# sch2.net
KiCad netlist of a schematic drawn in EAGLE
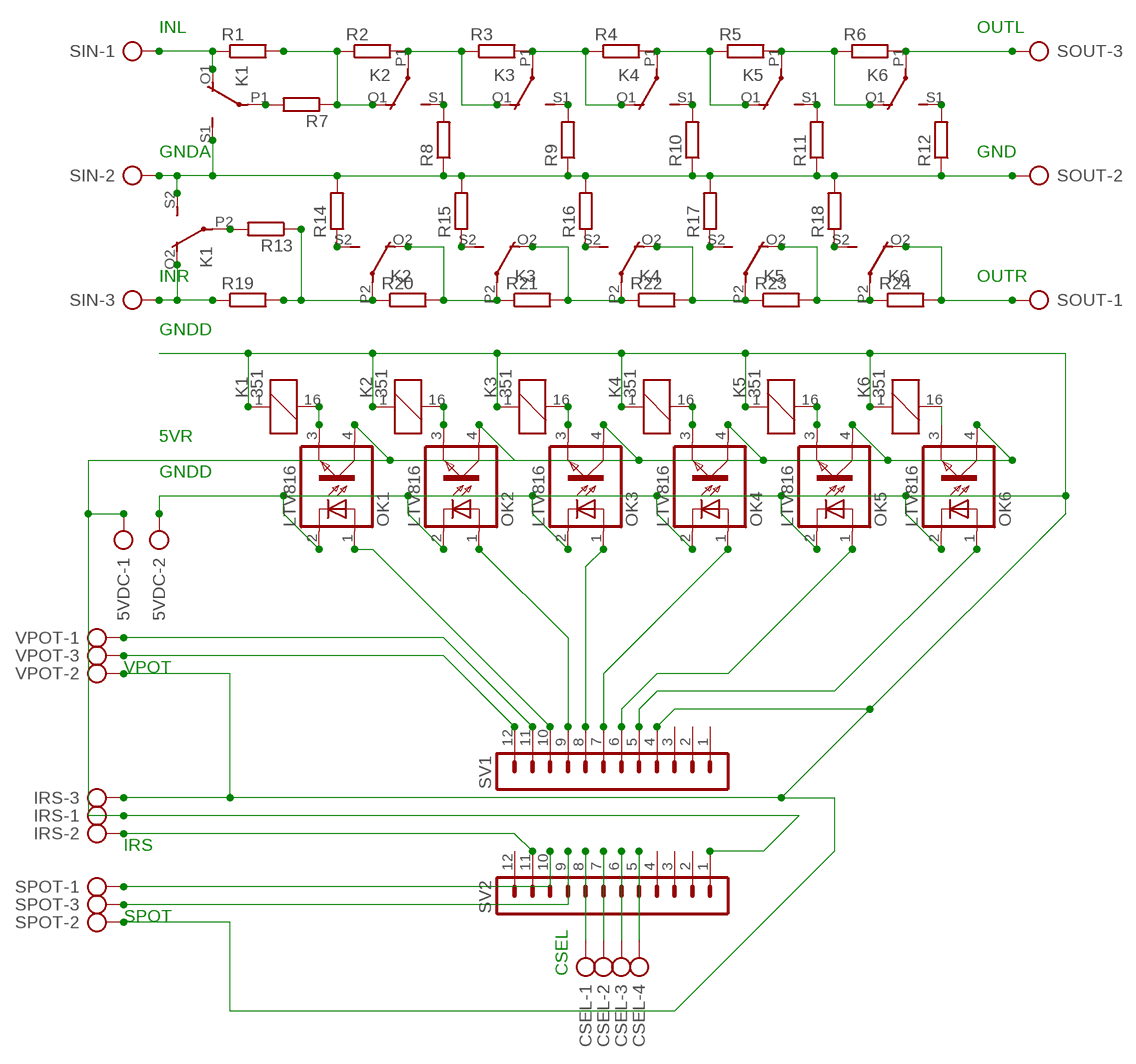
[diagram p0: schematic, sheet 1]

(export (version "E")
  (design (tool "Eeschema 10.0.6"))
  (components
    (comp (ref "5VDC")
      (value "AK500/2")
      (footprint "eagle-import:AK500_2")
      (libsource (lib "eagle-import") (part "AK500/2"))
    )
    (comp (ref "CSEL")
      (value "AK500/4")
      (footprint "eagle-import:AK500_4")
      (libsource (lib "eagle-import") (part "AK500/4"))
    )
    (comp (ref "IRS")
      (value "AK500/3")
      (footprint "eagle-import:AK500_3")
      (libsource (lib "eagle-import") (part "AK500/3"))
    )
    (comp (ref "K1")
      (value "351")
      (footprint "eagle-import:351")
      (libsource (lib "eagle-import") (part "351"))
    )
    (comp (ref "K2")
      (value "351")
      (footprint "eagle-import:351")
      (libsource (lib "eagle-import") (part "351"))
    )
    (comp (ref "K3")
      (value "351")
      (footprint "eagle-import:351")
      (libsource (lib "eagle-import") (part "351"))
    )
    (comp (ref "K4")
      (value "351")
      (footprint "eagle-import:351")
      (libsource (lib "eagle-import") (part "351"))
    )
    (comp (ref "K5")
      (value "351")
      (footprint "eagle-import:351")
      (libsource (lib "eagle-import") (part "351"))
    )
    (comp (ref "K6")
      (value "351")
      (footprint "eagle-import:351")
      (libsource (lib "eagle-import") (part "351"))
    )
    (comp (ref "OK1")
      (value "LTV816")
      (footprint "eagle-import:DIL04")
      (libsource (lib "eagle-import") (part "LTV816"))
    )
    (comp (ref "OK2")
      (value "LTV816")
      (footprint "eagle-import:DIL04")
      (libsource (lib "eagle-import") (part "LTV816"))
    )
    (comp (ref "OK3")
      (value "LTV816")
      (footprint "eagle-import:DIL04")
      (libsource (lib "eagle-import") (part "LTV816"))
    )
    (comp (ref "OK4")
      (value "LTV816")
      (footprint "eagle-import:DIL04")
      (libsource (lib "eagle-import") (part "LTV816"))
    )
    (comp (ref "OK5")
      (value "LTV816")
      (footprint "eagle-import:DIL04")
      (libsource (lib "eagle-import") (part "LTV816"))
    )
    (comp (ref "OK6")
      (value "LTV816")
      (footprint "eagle-import:DIL04")
      (libsource (lib "eagle-import") (part "LTV816"))
    )
    (comp (ref "R1")
      (value "R-EU_0204/7")
      (footprint "eagle-import:0204_7")
      (libsource (lib "eagle-import") (part "R-EU_0204/7"))
    )
    (comp (ref "R2")
      (value "R-EU_0204/7")
      (footprint "eagle-import:0204_7")
      (libsource (lib "eagle-import") (part "R-EU_0204/7"))
    )
    (comp (ref "R3")
      (value "R-EU_0204/7")
      (footprint "eagle-import:0204_7")
      (libsource (lib "eagle-import") (part "R-EU_0204/7"))
    )
    (comp (ref "R4")
      (value "R-EU_0204/7")
      (footprint "eagle-import:0204_7")
      (libsource (lib "eagle-import") (part "R-EU_0204/7"))
    )
    (comp (ref "R5")
      (value "R-EU_0204/7")
      (footprint "eagle-import:0204_7")
      (libsource (lib "eagle-import") (part "R-EU_0204/7"))
    )
    (comp (ref "R6")
      (value "R-EU_0204/7")
      (footprint "eagle-import:0204_7")
      (libsource (lib "eagle-import") (part "R-EU_0204/7"))
    )
    (comp (ref "R7")
      (value "R-EU_0204/7")
      (footprint "eagle-import:0204_7")
      (libsource (lib "eagle-import") (part "R-EU_0204/7"))
    )
    (comp (ref "R8")
      (value "R-EU_0204/7")
      (footprint "eagle-import:0204_7")
      (libsource (lib "eagle-import") (part "R-EU_0204/7"))
    )
    (comp (ref "R9")
      (value "R-EU_0204/7")
      (footprint "eagle-import:0204_7")
      (libsource (lib "eagle-import") (part "R-EU_0204/7"))
    )
    (comp (ref "R10")
      (value "R-EU_0204/7")
      (footprint "eagle-import:0204_7")
      (libsource (lib "eagle-import") (part "R-EU_0204/7"))
    )
    (comp (ref "R11")
      (value "R-EU_0204/7")
      (footprint "eagle-import:0204_7")
      (libsource (lib "eagle-import") (part "R-EU_0204/7"))
    )
    (comp (ref "R12")
      (value "R-EU_0204/7")
      (footprint "eagle-import:0204_7")
      (libsource (lib "eagle-import") (part "R-EU_0204/7"))
    )
    (comp (ref "R13")
      (value "R-EU_0204/7")
      (footprint "eagle-import:0204_7")
      (libsource (lib "eagle-import") (part "R-EU_0204/7"))
    )
    (comp (ref "R14")
      (value "R-EU_0204/7")
      (footprint "eagle-import:0204_7")
      (libsource (lib "eagle-import") (part "R-EU_0204/7"))
    )
    (comp (ref "R15")
      (value "R-EU_0204/7")
      (footprint "eagle-import:0204_7")
      (libsource (lib "eagle-import") (part "R-EU_0204/7"))
    )
    (comp (ref "R16")
      (value "R-EU_0204/7")
      (footprint "eagle-import:0204_7")
      (libsource (lib "eagle-import") (part "R-EU_0204/7"))
    )
    (comp (ref "R17")
      (value "R-EU_0204/7")
      (footprint "eagle-import:0204_7")
      (libsource (lib "eagle-import") (part "R-EU_0204/7"))
    )
    (comp (ref "R18")
      (value "R-EU_0204/7")
      (footprint "eagle-import:0204_7")
      (libsource (lib "eagle-import") (part "R-EU_0204/7"))
    )
    (comp (ref "R19")
      (value "R-EU_0204/7")
      (footprint "eagle-import:0204_7")
      (libsource (lib "eagle-import") (part "R-EU_0204/7"))
    )
    (comp (ref "R20")
      (value "R-EU_0204/7")
      (footprint "eagle-import:0204_7")
      (libsource (lib "eagle-import") (part "R-EU_0204/7"))
    )
    (comp (ref "R21")
      (value "R-EU_0204/7")
      (footprint "eagle-import:0204_7")
      (libsource (lib "eagle-import") (part "R-EU_0204/7"))
    )
    (comp (ref "R22")
      (value "R-EU_0204/7")
      (footprint "eagle-import:0204_7")
      (libsource (lib "eagle-import") (part "R-EU_0204/7"))
    )
    (comp (ref "R23")
      (value "R-EU_0204/7")
      (footprint "eagle-import:0204_7")
      (libsource (lib "eagle-import") (part "R-EU_0204/7"))
    )
    (comp (ref "R24")
      (value "R-EU_0204/7")
      (footprint "eagle-import:0204_7")
      (libsource (lib "eagle-import") (part "R-EU_0204/7"))
    )
    (comp (ref "SIN")
      (value "AK500/3")
      (footprint "eagle-import:AK500_3")
      (libsource (lib "eagle-import") (part "AK500/3"))
    )
    (comp (ref "SOUT")
      (value "AK500/3")
      (footprint "eagle-import:AK500_3")
      (libsource (lib "eagle-import") (part "AK500/3"))
    )
    (comp (ref "SPOT")
      (value "AK500/3")
      (footprint "eagle-import:AK500_3")
      (libsource (lib "eagle-import") (part "AK500/3"))
    )
    (comp (ref "SV1")
      (value "MA12-1")
      (footprint "eagle-import:MA12-1")
      (libsource (lib "eagle-import") (part "MA12-1"))
    )
    (comp (ref "SV2")
      (value "MA12-1")
      (footprint "eagle-import:MA12-1")
      (libsource (lib "eagle-import") (part "MA12-1"))
    )
    (comp (ref "VPOT")
      (value "AK500/3")
      (footprint "eagle-import:AK500_3")
      (libsource (lib "eagle-import") (part "AK500/3"))
    )
  )
  (nets
    (net (code "1") (name "Net-(5VDCA-KL)") (class "Default")
      (node (ref "5VDC") (pin "1") (pinfunction "KL_1") (pintype "passive"))
      (node (ref "IRS") (pin "1") (pinfunction "KL_1") (pintype "passive"))
      (node (ref "OK1") (pin "4") (pinfunction "COL_4") (pintype "passive"))
      (node (ref "OK2") (pin "4") (pinfunction "COL_4") (pintype "passive"))
      (node (ref "OK3") (pin "4") (pinfunction "COL_4") (pintype "passive"))
      (node (ref "OK4") (pin "4") (pinfunction "COL_4") (pintype "passive"))
      (node (ref "OK5") (pin "4") (pinfunction "COL_4") (pintype "passive"))
      (node (ref "OK6") (pin "4") (pinfunction "COL_4") (pintype "passive"))
      (node (ref "SV2") (pin "1") (pinfunction "1_1") (pintype "passive"))
    )
    (net (code "2") (name "Net-(5VDCB-KL)") (class "Default")
      (node (ref "5VDC") (pin "2") (pinfunction "KL_2") (pintype "passive"))
      (node (ref "IRS") (pin "3") (pinfunction "KL_3") (pintype "passive"))
      (node (ref "K1") (pin "1") (pinfunction "1_1") (pintype "passive"))
      (node (ref "K2") (pin "1") (pinfunction "1_1") (pintype "passive"))
      (node (ref "K3") (pin "1") (pinfunction "1_1") (pintype "passive"))
      (node (ref "K4") (pin "1") (pinfunction "1_1") (pintype "passive"))
      (node (ref "K5") (pin "1") (pinfunction "1_1") (pintype "passive"))
      (node (ref "K6") (pin "1") (pinfunction "1_1") (pintype "passive"))
      (node (ref "OK1") (pin "2") (pinfunction "C_2") (pintype "passive"))
      (node (ref "OK2") (pin "2") (pinfunction "C_2") (pintype "passive"))
      (node (ref "OK3") (pin "2") (pinfunction "C_2") (pintype "passive"))
      (node (ref "OK4") (pin "2") (pinfunction "C_2") (pintype "passive"))
      (node (ref "OK5") (pin "2") (pinfunction "C_2") (pintype "passive"))
      (node (ref "OK6") (pin "2") (pinfunction "C_2") (pintype "passive"))
      (node (ref "SPOT") (pin "2") (pinfunction "KL_2") (pintype "passive"))
      (node (ref "SV1") (pin "4") (pinfunction "4_4") (pintype "passive"))
      (node (ref "VPOT") (pin "2") (pinfunction "KL_2") (pintype "passive"))
    )
    (net (code "3") (name "Net-(CSELA-KL)") (class "Default")
      (node (ref "CSEL") (pin "1") (pinfunction "KL_1") (pintype "passive"))
      (node (ref "SV2") (pin "8") (pinfunction "8_8") (pintype "passive"))
    )
    (net (code "4") (name "Net-(CSELB-KL)") (class "Default")
      (node (ref "CSEL") (pin "2") (pinfunction "KL_2") (pintype "passive"))
      (node (ref "SV2") (pin "7") (pinfunction "7_7") (pintype "passive"))
    )
    (net (code "5") (name "Net-(CSELC-KL)") (class "Default")
      (node (ref "CSEL") (pin "3") (pinfunction "KL_3") (pintype "passive"))
      (node (ref "SV2") (pin "6") (pinfunction "6_6") (pintype "passive"))
    )
    (net (code "6") (name "Net-(CSELD-KL)") (class "Default")
      (node (ref "CSEL") (pin "4") (pinfunction "KL_4") (pintype "passive"))
      (node (ref "SV2") (pin "5") (pinfunction "5_5") (pintype "passive"))
    )
    (net (code "7") (name "Net-(IRSB-KL)") (class "Default")
      (node (ref "IRS") (pin "2") (pinfunction "KL_2") (pintype "passive"))
      (node (ref "SV2") (pin "11") (pinfunction "11_11") (pintype "passive"))
    )
    (net (code "8") (name "Net-(K1A-2)") (class "Default")
      (node (ref "K1") (pin "16") (pinfunction "2_16") (pintype "passive"))
      (node (ref "OK1") (pin "3") (pinfunction "EMIT_3") (pintype "passive"))
    )
    (net (code "9") (name "Net-(K1B-O)") (class "Default")
      (node (ref "K1") (pin "O1") (pinfunction "O_O1") (pintype "passive"))
      (node (ref "R1") (pin "1") (pinfunction "1_1") (pintype "passive"))
      (node (ref "SIN") (pin "1") (pinfunction "KL_1") (pintype "passive"))
    )
    (net (code "10") (name "Net-(K1B-P)") (class "Default")
      (node (ref "K1") (pin "P1") (pinfunction "P_P1") (pintype "passive"))
      (node (ref "R7") (pin "2") (pinfunction "2_2") (pintype "passive"))
    )
    (net (code "11") (name "Net-(K1B-S)") (class "Default")
      (node (ref "K1") (pin "S1") (pinfunction "S_S1") (pintype "passive"))
      (node (ref "K1") (pin "S2") (pinfunction "S_S2") (pintype "passive"))
      (node (ref "R10") (pin "1") (pinfunction "1_1") (pintype "passive"))
      (node (ref "R11") (pin "1") (pinfunction "1_1") (pintype "passive"))
      (node (ref "R12") (pin "1") (pinfunction "1_1") (pintype "passive"))
      (node (ref "R14") (pin "2") (pinfunction "2_2") (pintype "passive"))
      (node (ref "R15") (pin "2") (pinfunction "2_2") (pintype "passive"))
      (node (ref "R16") (pin "2") (pinfunction "2_2") (pintype "passive"))
      (node (ref "R17") (pin "2") (pinfunction "2_2") (pintype "passive"))
      (node (ref "R18") (pin "2") (pinfunction "2_2") (pintype "passive"))
      (node (ref "R8") (pin "1") (pinfunction "1_1") (pintype "passive"))
      (node (ref "R9") (pin "1") (pinfunction "1_1") (pintype "passive"))
      (node (ref "SIN") (pin "2") (pinfunction "KL_2") (pintype "passive"))
      (node (ref "SOUT") (pin "2") (pinfunction "KL_2") (pintype "passive"))
    )
    (net (code "12") (name "Net-(K1C-O)") (class "Default")
      (node (ref "K1") (pin "O2") (pinfunction "O_O2") (pintype "passive"))
      (node (ref "R19") (pin "1") (pinfunction "1_1") (pintype "passive"))
      (node (ref "SIN") (pin "3") (pinfunction "KL_3") (pintype "passive"))
    )
    (net (code "13") (name "Net-(K1C-P)") (class "Default")
      (node (ref "K1") (pin "P2") (pinfunction "P_P2") (pintype "passive"))
      (node (ref "R13") (pin "2") (pinfunction "2_2") (pintype "passive"))
    )
    (net (code "14") (name "Net-(K2A-2)") (class "Default")
      (node (ref "K2") (pin "16") (pinfunction "2_16") (pintype "passive"))
      (node (ref "OK2") (pin "3") (pinfunction "EMIT_3") (pintype "passive"))
    )
    (net (code "15") (name "Net-(K2B-O)") (class "Default")
      (node (ref "K2") (pin "O1") (pinfunction "O_O1") (pintype "passive"))
      (node (ref "R1") (pin "2") (pinfunction "2_2") (pintype "passive"))
      (node (ref "R2") (pin "1") (pinfunction "1_1") (pintype "passive"))
      (node (ref "R7") (pin "1") (pinfunction "1_1") (pintype "passive"))
    )
    (net (code "16") (name "Net-(K2B-P)") (class "Default")
      (node (ref "K2") (pin "P1") (pinfunction "P_P1") (pintype "passive"))
      (node (ref "K3") (pin "O1") (pinfunction "O_O1") (pintype "passive"))
      (node (ref "R2") (pin "2") (pinfunction "2_2") (pintype "passive"))
      (node (ref "R3") (pin "1") (pinfunction "1_1") (pintype "passive"))
    )
    (net (code "17") (name "Net-(K2B-S)") (class "Default")
      (node (ref "K2") (pin "S1") (pinfunction "S_S1") (pintype "passive"))
      (node (ref "R8") (pin "2") (pinfunction "2_2") (pintype "passive"))
    )
    (net (code "18") (name "Net-(K2C-O)") (class "Default")
      (node (ref "K2") (pin "O2") (pinfunction "O_O2") (pintype "passive"))
      (node (ref "K3") (pin "P2") (pinfunction "P_P2") (pintype "passive"))
      (node (ref "R20") (pin "2") (pinfunction "2_2") (pintype "passive"))
      (node (ref "R21") (pin "1") (pinfunction "1_1") (pintype "passive"))
    )
    (net (code "19") (name "Net-(K2C-P)") (class "Default")
      (node (ref "K2") (pin "P2") (pinfunction "P_P2") (pintype "passive"))
      (node (ref "R13") (pin "1") (pinfunction "1_1") (pintype "passive"))
      (node (ref "R19") (pin "2") (pinfunction "2_2") (pintype "passive"))
      (node (ref "R20") (pin "1") (pinfunction "1_1") (pintype "passive"))
    )
    (net (code "20") (name "Net-(K2C-S)") (class "Default")
      (node (ref "K2") (pin "S2") (pinfunction "S_S2") (pintype "passive"))
      (node (ref "R14") (pin "1") (pinfunction "1_1") (pintype "passive"))
    )
    (net (code "21") (name "Net-(K3A-2)") (class "Default")
      (node (ref "K3") (pin "16") (pinfunction "2_16") (pintype "passive"))
      (node (ref "OK3") (pin "3") (pinfunction "EMIT_3") (pintype "passive"))
    )
    (net (code "22") (name "Net-(K3B-P)") (class "Default")
      (node (ref "K3") (pin "P1") (pinfunction "P_P1") (pintype "passive"))
      (node (ref "K4") (pin "O1") (pinfunction "O_O1") (pintype "passive"))
      (node (ref "R3") (pin "2") (pinfunction "2_2") (pintype "passive"))
      (node (ref "R4") (pin "1") (pinfunction "1_1") (pintype "passive"))
    )
    (net (code "23") (name "Net-(K3B-S)") (class "Default")
      (node (ref "K3") (pin "S1") (pinfunction "S_S1") (pintype "passive"))
      (node (ref "R9") (pin "2") (pinfunction "2_2") (pintype "passive"))
    )
    (net (code "24") (name "Net-(K3C-O)") (class "Default")
      (node (ref "K3") (pin "O2") (pinfunction "O_O2") (pintype "passive"))
      (node (ref "K4") (pin "P2") (pinfunction "P_P2") (pintype "passive"))
      (node (ref "R21") (pin "2") (pinfunction "2_2") (pintype "passive"))
      (node (ref "R22") (pin "1") (pinfunction "1_1") (pintype "passive"))
    )
    (net (code "25") (name "Net-(K3C-S)") (class "Default")
      (node (ref "K3") (pin "S2") (pinfunction "S_S2") (pintype "passive"))
      (node (ref "R15") (pin "1") (pinfunction "1_1") (pintype "passive"))
    )
    (net (code "26") (name "Net-(K4A-2)") (class "Default")
      (node (ref "K4") (pin "16") (pinfunction "2_16") (pintype "passive"))
      (node (ref "OK4") (pin "3") (pinfunction "EMIT_3") (pintype "passive"))
    )
    (net (code "27") (name "Net-(K4B-P)") (class "Default")
      (node (ref "K4") (pin "P1") (pinfunction "P_P1") (pintype "passive"))
      (node (ref "K5") (pin "O1") (pinfunction "O_O1") (pintype "passive"))
      (node (ref "R4") (pin "2") (pinfunction "2_2") (pintype "passive"))
      (node (ref "R5") (pin "1") (pinfunction "1_1") (pintype "passive"))
    )
    (net (code "28") (name "Net-(K4B-S)") (class "Default")
      (node (ref "K4") (pin "S1") (pinfunction "S_S1") (pintype "passive"))
      (node (ref "R10") (pin "2") (pinfunction "2_2") (pintype "passive"))
    )
    (net (code "29") (name "Net-(K4C-O)") (class "Default")
      (node (ref "K4") (pin "O2") (pinfunction "O_O2") (pintype "passive"))
      (node (ref "K5") (pin "P2") (pinfunction "P_P2") (pintype "passive"))
      (node (ref "R22") (pin "2") (pinfunction "2_2") (pintype "passive"))
      (node (ref "R23") (pin "1") (pinfunction "1_1") (pintype "passive"))
    )
    (net (code "30") (name "Net-(K4C-S)") (class "Default")
      (node (ref "K4") (pin "S2") (pinfunction "S_S2") (pintype "passive"))
      (node (ref "R16") (pin "1") (pinfunction "1_1") (pintype "passive"))
    )
    (net (code "31") (name "Net-(K5A-2)") (class "Default")
      (node (ref "K5") (pin "16") (pinfunction "2_16") (pintype "passive"))
      (node (ref "OK5") (pin "3") (pinfunction "EMIT_3") (pintype "passive"))
    )
    (net (code "32") (name "Net-(K5B-P)") (class "Default")
      (node (ref "K5") (pin "P1") (pinfunction "P_P1") (pintype "passive"))
      (node (ref "K6") (pin "O1") (pinfunction "O_O1") (pintype "passive"))
      (node (ref "R5") (pin "2") (pinfunction "2_2") (pintype "passive"))
      (node (ref "R6") (pin "1") (pinfunction "1_1") (pintype "passive"))
    )
    (net (code "33") (name "Net-(K5B-S)") (class "Default")
      (node (ref "K5") (pin "S1") (pinfunction "S_S1") (pintype "passive"))
      (node (ref "R11") (pin "2") (pinfunction "2_2") (pintype "passive"))
    )
    (net (code "34") (name "Net-(K5C-O)") (class "Default")
      (node (ref "K5") (pin "O2") (pinfunction "O_O2") (pintype "passive"))
      (node (ref "K6") (pin "P2") (pinfunction "P_P2") (pintype "passive"))
      (node (ref "R23") (pin "2") (pinfunction "2_2") (pintype "passive"))
      (node (ref "R24") (pin "1") (pinfunction "1_1") (pintype "passive"))
    )
    (net (code "35") (name "Net-(K5C-S)") (class "Default")
      (node (ref "K5") (pin "S2") (pinfunction "S_S2") (pintype "passive"))
      (node (ref "R17") (pin "1") (pinfunction "1_1") (pintype "passive"))
    )
    (net (code "36") (name "Net-(K6A-2)") (class "Default")
      (node (ref "K6") (pin "16") (pinfunction "2_16") (pintype "passive"))
      (node (ref "OK6") (pin "3") (pinfunction "EMIT_3") (pintype "passive"))
    )
    (net (code "37") (name "Net-(K6B-P)") (class "Default")
      (node (ref "K6") (pin "P1") (pinfunction "P_P1") (pintype "passive"))
      (node (ref "R6") (pin "2") (pinfunction "2_2") (pintype "passive"))
      (node (ref "SOUT") (pin "3") (pinfunction "KL_3") (pintype "passive"))
    )
    (net (code "38") (name "Net-(K6B-S)") (class "Default")
      (node (ref "K6") (pin "S1") (pinfunction "S_S1") (pintype "passive"))
      (node (ref "R12") (pin "2") (pinfunction "2_2") (pintype "passive"))
    )
    (net (code "39") (name "Net-(K6C-O)") (class "Default")
      (node (ref "K6") (pin "O2") (pinfunction "O_O2") (pintype "passive"))
      (node (ref "R24") (pin "2") (pinfunction "2_2") (pintype "passive"))
      (node (ref "SOUT") (pin "1") (pinfunction "KL_1") (pintype "passive"))
    )
    (net (code "40") (name "Net-(K6C-S)") (class "Default")
      (node (ref "K6") (pin "S2") (pinfunction "S_S2") (pintype "passive"))
      (node (ref "R18") (pin "1") (pinfunction "1_1") (pintype "passive"))
    )
    (net (code "41") (name "Net-(OK1-A)") (class "Default")
      (node (ref "OK1") (pin "1") (pinfunction "A_1") (pintype "passive"))
      (node (ref "SV1") (pin "10") (pinfunction "10_10") (pintype "passive"))
    )
    (net (code "42") (name "Net-(OK2-A)") (class "Default")
      (node (ref "OK2") (pin "1") (pinfunction "A_1") (pintype "passive"))
      (node (ref "SV1") (pin "9") (pinfunction "9_9") (pintype "passive"))
    )
    (net (code "43") (name "Net-(OK3-A)") (class "Default")
      (node (ref "OK3") (pin "1") (pinfunction "A_1") (pintype "passive"))
      (node (ref "SV1") (pin "8") (pinfunction "8_8") (pintype "passive"))
    )
    (net (code "44") (name "Net-(OK4-A)") (class "Default")
      (node (ref "OK4") (pin "1") (pinfunction "A_1") (pintype "passive"))
      (node (ref "SV1") (pin "7") (pinfunction "7_7") (pintype "passive"))
    )
    (net (code "45") (name "Net-(OK5-A)") (class "Default")
      (node (ref "OK5") (pin "1") (pinfunction "A_1") (pintype "passive"))
      (node (ref "SV1") (pin "6") (pinfunction "6_6") (pintype "passive"))
    )
    (net (code "46") (name "Net-(OK6-A)") (class "Default")
      (node (ref "OK6") (pin "1") (pinfunction "A_1") (pintype "passive"))
      (node (ref "SV1") (pin "5") (pinfunction "5_5") (pintype "passive"))
    )
    (net (code "47") (name "Net-(SPOTA-KL)") (class "Default")
      (node (ref "SPOT") (pin "1") (pinfunction "KL_1") (pintype "passive"))
      (node (ref "SV2") (pin "10") (pinfunction "10_10") (pintype "passive"))
    )
    (net (code "48") (name "Net-(SPOTC-KL)") (class "Default")
      (node (ref "SPOT") (pin "3") (pinfunction "KL_3") (pintype "passive"))
      (node (ref "SV2") (pin "9") (pinfunction "9_9") (pintype "passive"))
    )
    (net (code "49") (name "Net-(VPOTA-KL)") (class "Default")
      (node (ref "SV1") (pin "11") (pinfunction "11_11") (pintype "passive"))
      (node (ref "VPOT") (pin "1") (pinfunction "KL_1") (pintype "passive"))
    )
    (net (code "50") (name "Net-(VPOTC-KL)") (class "Default")
      (node (ref "SV1") (pin "12") (pinfunction "12_12") (pintype "passive"))
      (node (ref "VPOT") (pin "3") (pinfunction "KL_3") (pintype "passive"))
    )
    (net (code "51") (name "unconnected-(SV1-Pad1)") (class "Default")
      (node (ref "SV1") (pin "1") (pinfunction "1_1") (pintype "passive"))
    )
    (net (code "52") (name "unconnected-(SV1-Pad2)") (class "Default")
      (node (ref "SV1") (pin "2") (pinfunction "2_2") (pintype "passive"))
    )
    (net (code "53") (name "unconnected-(SV1-Pad3)") (class "Default")
      (node (ref "SV1") (pin "3") (pinfunction "3_3") (pintype "passive"))
    )
    (net (code "54") (name "unconnected-(SV2-Pad2)") (class "Default")
      (node (ref "SV2") (pin "2") (pinfunction "2_2") (pintype "passive"))
    )
    (net (code "55") (name "unconnected-(SV2-Pad3)") (class "Default")
      (node (ref "SV2") (pin "3") (pinfunction "3_3") (pintype "passive"))
    )
    (net (code "56") (name "unconnected-(SV2-Pad4)") (class "Default")
      (node (ref "SV2") (pin "4") (pinfunction "4_4") (pintype "passive"))
    )
    (net (code "57") (name "unconnected-(SV2-Pad12)") (class "Default")
      (node (ref "SV2") (pin "12") (pinfunction "12_12") (pintype "passive"))
    )
  )
)
